# Banker_VHDCI_2_EDGE.net
KiCad netlist of a schematic drawn in Altium Designer
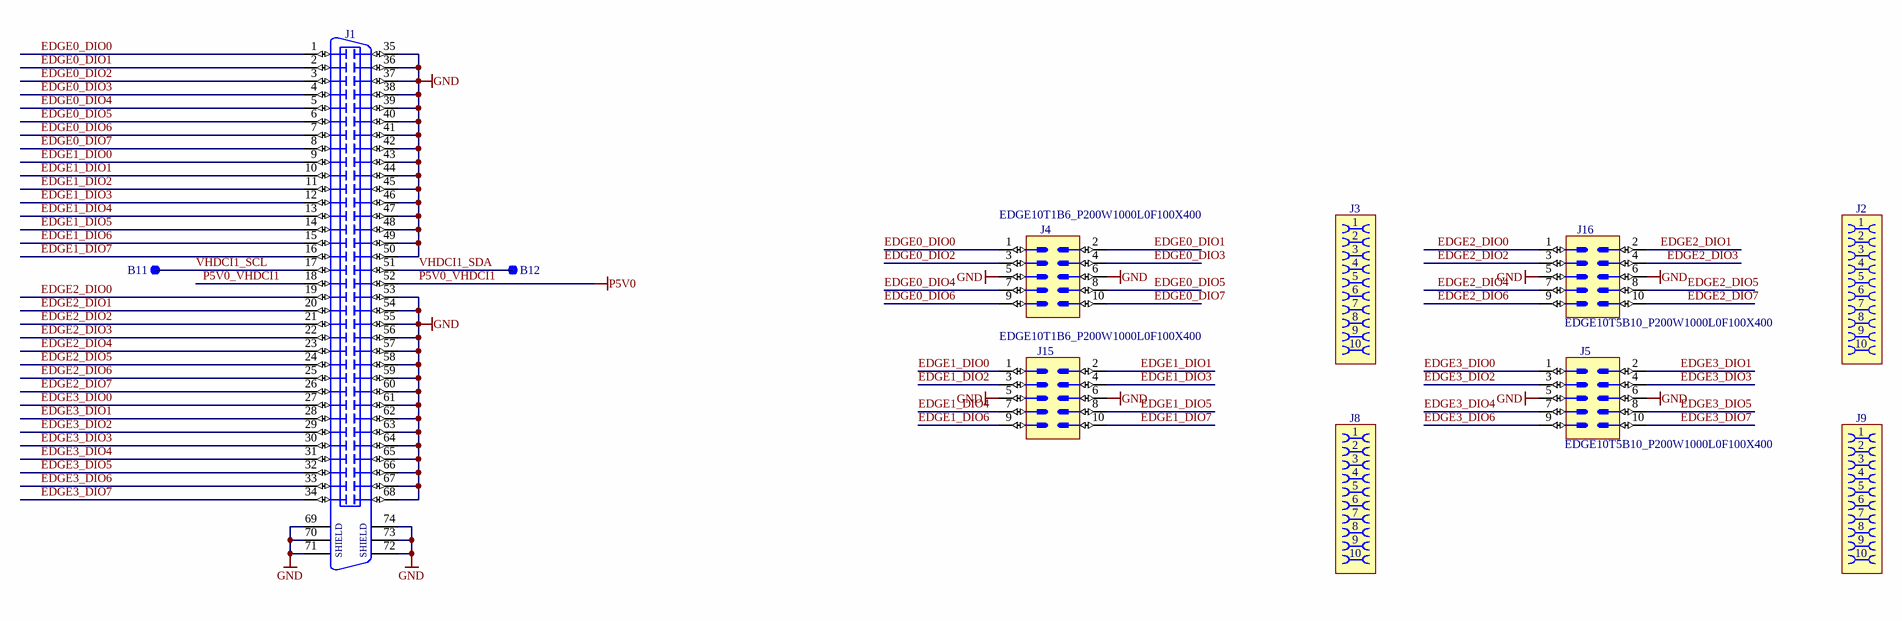
[diagram p0: Banker_VHDCI_2_EDGE.SchDoc]

(export (version "E")
  (design (tool "Eeschema 10.0.6"))
  (components
    (comp (ref "B11")
      (value "SMD Pad")
      (footprint "C100")
      (description "Through Hole Pad")
      (fields (field (name "PART NUMBER") "SMD_PAD_D1MM") (field (name "AUTHOR") "CERN DEM JLC"))
      (libsource (lib "Eletro-mechanical") (part "Single SMD Pad (Round)"))
    )
    (comp (ref "B12")
      (value "SMD Pad")
      (footprint "C100")
      (description "Through Hole Pad")
      (fields (field (name "PART NUMBER") "SMD_PAD_D1MM") (field (name "AUTHOR") "CERN DEM JLC"))
      (libsource (lib "Eletro-mechanical") (part "Single SMD Pad (Round)"))
    )
    (comp (ref "J1")
      (value "VHDCI")
      (footprint "MOLEX_73776-0201")
      (description "0.80mm Pitch, 68 Contacts, Ultra+ VHDCI Surface Mount Vertical Receptacle")
      (fields
        (field (name "PART NUMBER") "MOLEX_73776-0201")
        (field (name "MANUFACTURER") "MOLEX")
        (field (name "AUTHOR") "CERN DEM JLC")
      )
      (libsource (lib "Connectors") (part "MOLEX_73776-0201"))
    )
    (comp (ref "J2")
      (value "~")
      (footprint "AVX_00 9159 010 061 916")
      (description "Open Ended Card Edge Connector, 9159 Series")
      (fields
        (field (name "PART NUMBER") "AVX_00 9159 010 061 916")
        (field (name "MANUFACTURER") "AVX")
        (field (name "AUTHOR") "CERN DEM MR")
      )
      (libsource (lib "Connectors") (part "AVX_00 9159 010 061 916"))
    )
    (comp (ref "J3")
      (value "~")
      (footprint "AVX_00 9159 010 061 916")
      (description "Open Ended Card Edge Connector, 9159 Series")
      (fields
        (field (name "PART NUMBER") "AVX_00 9159 010 061 916")
        (field (name "MANUFACTURER") "AVX")
        (field (name "AUTHOR") "CERN DEM MR")
      )
      (libsource (lib "Connectors") (part "AVX_00 9159 010 061 916"))
    )
    (comp (ref "J4")
      (value "~")
      (footprint "EDGE10T1B6_P200W1000L0F100X400")
      (description "PCB Edge Connector 10 (2x5)")
      (fields
        (field (name "PART NUMBER") "EDGE10T1B6_P200W1000L0F100X400")
        (field (name "AUTHOR") "CERN DEM MR")
      )
      (libsource (lib "Connectors") (part "PCB Edge Connector 10 (2x5)"))
    )
    (comp (ref "J5")
      (value "~")
      (footprint "EDGE10T5B10_P200W1000L0F100X400")
      (description "PCB Edge Connector 10 (2x5)")
      (fields
        (field (name "PART NUMBER") "EDGE10T5B10_P200W1000L0F100X400")
        (field (name "AUTHOR") "CERN DEM MR")
      )
      (libsource (lib "Connectors") (part "PCB Edge Connector 10 (2x5)"))
    )
    (comp (ref "J8")
      (value "~")
      (footprint "AVX_00 9159 010 061 916")
      (description "Open Ended Card Edge Connector, 9159 Series")
      (fields
        (field (name "PART NUMBER") "AVX_00 9159 010 061 916")
        (field (name "MANUFACTURER") "AVX")
        (field (name "AUTHOR") "CERN DEM MR")
      )
      (libsource (lib "Connectors") (part "AVX_00 9159 010 061 916"))
    )
    (comp (ref "J9")
      (value "~")
      (footprint "AVX_00 9159 010 061 916")
      (description "Open Ended Card Edge Connector, 9159 Series")
      (fields
        (field (name "PART NUMBER") "AVX_00 9159 010 061 916")
        (field (name "MANUFACTURER") "AVX")
        (field (name "AUTHOR") "CERN DEM MR")
      )
      (libsource (lib "Connectors") (part "AVX_00 9159 010 061 916"))
    )
    (comp (ref "J15")
      (value "~")
      (footprint "EDGE10T1B6_P200W1000L0F100X400")
      (description "PCB Edge Connector 10 (2x5)")
      (fields
        (field (name "PART NUMBER") "EDGE10T1B6_P200W1000L0F100X400")
        (field (name "AUTHOR") "CERN DEM MR")
      )
      (libsource (lib "Connectors") (part "PCB Edge Connector 10 (2x5)"))
    )
    (comp (ref "J16")
      (value "~")
      (footprint "EDGE10T5B10_P200W1000L0F100X400")
      (description "PCB Edge Connector 10 (2x5)")
      (fields
        (field (name "PART NUMBER") "EDGE10T5B10_P200W1000L0F100X400")
        (field (name "AUTHOR") "CERN DEM MR")
      )
      (libsource (lib "Connectors") (part "PCB Edge Connector 10 (2x5)"))
    )
  )
  (nets
    (net (code "1") (name "/EDGE0_DIO0") (class "Default")
      (node (ref "J1") (pin "1") (pinfunction "1_1") (pintype "bidirectional"))
      (node (ref "J4") (pin "1") (pinfunction "1_1") (pintype "bidirectional"))
    )
    (net (code "2") (name "/EDGE0_DIO1") (class "Default")
      (node (ref "J1") (pin "2") (pinfunction "2_2") (pintype "bidirectional"))
      (node (ref "J4") (pin "2") (pinfunction "2_2") (pintype "bidirectional"))
    )
    (net (code "3") (name "/EDGE0_DIO2") (class "Default")
      (node (ref "J1") (pin "3") (pinfunction "3_3") (pintype "bidirectional"))
      (node (ref "J4") (pin "3") (pinfunction "3_3") (pintype "bidirectional"))
    )
    (net (code "4") (name "/EDGE0_DIO3") (class "Default")
      (node (ref "J1") (pin "4") (pinfunction "4_4") (pintype "bidirectional"))
      (node (ref "J4") (pin "4") (pinfunction "4_4") (pintype "bidirectional"))
    )
    (net (code "5") (name "/EDGE0_DIO4") (class "Default")
      (node (ref "J1") (pin "5") (pinfunction "5_5") (pintype "bidirectional"))
      (node (ref "J4") (pin "7") (pinfunction "7_7") (pintype "bidirectional"))
    )
    (net (code "6") (name "/EDGE0_DIO5") (class "Default")
      (node (ref "J1") (pin "6") (pinfunction "6_6") (pintype "bidirectional"))
      (node (ref "J4") (pin "8") (pinfunction "8_8") (pintype "bidirectional"))
    )
    (net (code "7") (name "/EDGE0_DIO6") (class "Default")
      (node (ref "J1") (pin "7") (pinfunction "7_7") (pintype "bidirectional"))
      (node (ref "J4") (pin "9") (pinfunction "9_9") (pintype "bidirectional"))
    )
    (net (code "8") (name "/EDGE0_DIO7") (class "Default")
      (node (ref "J1") (pin "8") (pinfunction "8_8") (pintype "bidirectional"))
      (node (ref "J4") (pin "10") (pinfunction "10_10") (pintype "bidirectional"))
    )
    (net (code "9") (name "/EDGE1_DIO0") (class "Default")
      (node (ref "J1") (pin "9") (pinfunction "9_9") (pintype "bidirectional"))
      (node (ref "J15") (pin "1") (pinfunction "1_1") (pintype "bidirectional"))
    )
    (net (code "10") (name "/EDGE1_DIO1") (class "Default")
      (node (ref "J1") (pin "10") (pinfunction "10_10") (pintype "bidirectional"))
      (node (ref "J15") (pin "2") (pinfunction "2_2") (pintype "bidirectional"))
    )
    (net (code "11") (name "/EDGE1_DIO2") (class "Default")
      (node (ref "J1") (pin "11") (pinfunction "11_11") (pintype "bidirectional"))
      (node (ref "J15") (pin "3") (pinfunction "3_3") (pintype "bidirectional"))
    )
    (net (code "12") (name "/EDGE1_DIO3") (class "Default")
      (node (ref "J1") (pin "12") (pinfunction "12_12") (pintype "bidirectional"))
      (node (ref "J15") (pin "4") (pinfunction "4_4") (pintype "bidirectional"))
    )
    (net (code "13") (name "/EDGE1_DIO4") (class "Default")
      (node (ref "J1") (pin "13") (pinfunction "13_13") (pintype "bidirectional"))
      (node (ref "J15") (pin "7") (pinfunction "7_7") (pintype "bidirectional"))
    )
    (net (code "14") (name "/EDGE1_DIO5") (class "Default")
      (node (ref "J1") (pin "14") (pinfunction "14_14") (pintype "bidirectional"))
      (node (ref "J15") (pin "8") (pinfunction "8_8") (pintype "bidirectional"))
    )
    (net (code "15") (name "/EDGE1_DIO6") (class "Default")
      (node (ref "J1") (pin "15") (pinfunction "15_15") (pintype "bidirectional"))
      (node (ref "J15") (pin "9") (pinfunction "9_9") (pintype "bidirectional"))
    )
    (net (code "16") (name "/EDGE1_DIO7") (class "Default")
      (node (ref "J1") (pin "16") (pinfunction "16_16") (pintype "bidirectional"))
      (node (ref "J15") (pin "10") (pinfunction "10_10") (pintype "bidirectional"))
    )
    (net (code "17") (name "/EDGE2_DIO0") (class "Default")
      (node (ref "J1") (pin "19") (pinfunction "19_19") (pintype "bidirectional"))
      (node (ref "J16") (pin "1") (pinfunction "1_1") (pintype "bidirectional"))
    )
    (net (code "18") (name "/EDGE2_DIO1") (class "Default")
      (node (ref "J1") (pin "20") (pinfunction "20_20") (pintype "bidirectional"))
      (node (ref "J16") (pin "2") (pinfunction "2_2") (pintype "bidirectional"))
    )
    (net (code "19") (name "/EDGE2_DIO2") (class "Default")
      (node (ref "J1") (pin "21") (pinfunction "21_21") (pintype "bidirectional"))
      (node (ref "J16") (pin "3") (pinfunction "3_3") (pintype "bidirectional"))
    )
    (net (code "20") (name "/EDGE2_DIO3") (class "Default")
      (node (ref "J1") (pin "22") (pinfunction "22_22") (pintype "bidirectional"))
      (node (ref "J16") (pin "4") (pinfunction "4_4") (pintype "bidirectional"))
    )
    (net (code "21") (name "/EDGE2_DIO4") (class "Default")
      (node (ref "J1") (pin "23") (pinfunction "23_23") (pintype "bidirectional"))
      (node (ref "J16") (pin "7") (pinfunction "7_7") (pintype "bidirectional"))
    )
    (net (code "22") (name "/EDGE2_DIO5") (class "Default")
      (node (ref "J1") (pin "24") (pinfunction "24_24") (pintype "bidirectional"))
      (node (ref "J16") (pin "8") (pinfunction "8_8") (pintype "bidirectional"))
    )
    (net (code "23") (name "/EDGE2_DIO6") (class "Default")
      (node (ref "J1") (pin "25") (pinfunction "25_25") (pintype "bidirectional"))
      (node (ref "J16") (pin "9") (pinfunction "9_9") (pintype "bidirectional"))
    )
    (net (code "24") (name "/EDGE2_DIO7") (class "Default")
      (node (ref "J1") (pin "26") (pinfunction "26_26") (pintype "bidirectional"))
      (node (ref "J16") (pin "10") (pinfunction "10_10") (pintype "bidirectional"))
    )
    (net (code "25") (name "/EDGE3_DIO0") (class "Default")
      (node (ref "J1") (pin "27") (pinfunction "27_27") (pintype "bidirectional"))
      (node (ref "J5") (pin "1") (pinfunction "1_1") (pintype "bidirectional"))
    )
    (net (code "26") (name "/EDGE3_DIO1") (class "Default")
      (node (ref "J1") (pin "28") (pinfunction "28_28") (pintype "bidirectional"))
      (node (ref "J5") (pin "2") (pinfunction "2_2") (pintype "bidirectional"))
    )
    (net (code "27") (name "/EDGE3_DIO2") (class "Default")
      (node (ref "J1") (pin "29") (pinfunction "29_29") (pintype "bidirectional"))
      (node (ref "J5") (pin "3") (pinfunction "3_3") (pintype "bidirectional"))
    )
    (net (code "28") (name "/EDGE3_DIO3") (class "Default")
      (node (ref "J1") (pin "30") (pinfunction "30_30") (pintype "bidirectional"))
      (node (ref "J5") (pin "4") (pinfunction "4_4") (pintype "bidirectional"))
    )
    (net (code "29") (name "/EDGE3_DIO4") (class "Default")
      (node (ref "J1") (pin "31") (pinfunction "31_31") (pintype "bidirectional"))
      (node (ref "J5") (pin "7") (pinfunction "7_7") (pintype "bidirectional"))
    )
    (net (code "30") (name "/EDGE3_DIO5") (class "Default")
      (node (ref "J1") (pin "32") (pinfunction "32_32") (pintype "bidirectional"))
      (node (ref "J5") (pin "8") (pinfunction "8_8") (pintype "bidirectional"))
    )
    (net (code "31") (name "/EDGE3_DIO6") (class "Default")
      (node (ref "J1") (pin "33") (pinfunction "33_33") (pintype "bidirectional"))
      (node (ref "J5") (pin "9") (pinfunction "9_9") (pintype "bidirectional"))
    )
    (net (code "32") (name "/EDGE3_DIO7") (class "Default")
      (node (ref "J1") (pin "34") (pinfunction "34_34") (pintype "bidirectional"))
      (node (ref "J5") (pin "10") (pinfunction "10_10") (pintype "bidirectional"))
    )
    (net (code "33") (name "/VHDCI1_SCL") (class "Default")
      (node (ref "B11") (pin "1") (pinfunction "1_1") (pintype "bidirectional"))
      (node (ref "J1") (pin "17") (pinfunction "17_17") (pintype "bidirectional"))
    )
    (net (code "34") (name "/VHDCI1_SDA") (class "Default")
      (node (ref "B12") (pin "1") (pinfunction "1_1") (pintype "bidirectional"))
      (node (ref "J1") (pin "51") (pinfunction "51_51") (pintype "bidirectional"))
    )
    (net (code "35") (name "GND") (class "Default")
      (node (ref "J1") (pin "35") (pinfunction "35_35") (pintype "bidirectional"))
      (node (ref "J1") (pin "36") (pinfunction "36_36") (pintype "bidirectional"))
      (node (ref "J1") (pin "37") (pinfunction "37_37") (pintype "bidirectional"))
      (node (ref "J1") (pin "38") (pinfunction "38_38") (pintype "bidirectional"))
      (node (ref "J1") (pin "39") (pinfunction "39_39") (pintype "bidirectional"))
      (node (ref "J1") (pin "40") (pinfunction "40_40") (pintype "bidirectional"))
      (node (ref "J1") (pin "41") (pinfunction "41_41") (pintype "bidirectional"))
      (node (ref "J1") (pin "42") (pinfunction "42_42") (pintype "bidirectional"))
      (node (ref "J1") (pin "43") (pinfunction "43_43") (pintype "bidirectional"))
      (node (ref "J1") (pin "44") (pinfunction "44_44") (pintype "bidirectional"))
      (node (ref "J1") (pin "45") (pinfunction "45_45") (pintype "bidirectional"))
      (node (ref "J1") (pin "46") (pinfunction "46_46") (pintype "bidirectional"))
      (node (ref "J1") (pin "47") (pinfunction "47_47") (pintype "bidirectional"))
      (node (ref "J1") (pin "48") (pinfunction "48_48") (pintype "bidirectional"))
      (node (ref "J1") (pin "49") (pinfunction "49_49") (pintype "bidirectional"))
      (node (ref "J1") (pin "50") (pinfunction "50_50") (pintype "bidirectional"))
      (node (ref "J1") (pin "53") (pinfunction "53_53") (pintype "bidirectional"))
      (node (ref "J1") (pin "54") (pinfunction "54_54") (pintype "bidirectional"))
      (node (ref "J1") (pin "55") (pinfunction "55_55") (pintype "bidirectional"))
      (node (ref "J1") (pin "56") (pinfunction "56_56") (pintype "bidirectional"))
      (node (ref "J1") (pin "57") (pinfunction "57_57") (pintype "bidirectional"))
      (node (ref "J1") (pin "58") (pinfunction "58_58") (pintype "bidirectional"))
      (node (ref "J1") (pin "59") (pinfunction "59_59") (pintype "bidirectional"))
      (node (ref "J1") (pin "60") (pinfunction "60_60") (pintype "bidirectional"))
      (node (ref "J1") (pin "61") (pinfunction "61_61") (pintype "bidirectional"))
      (node (ref "J1") (pin "62") (pinfunction "62_62") (pintype "bidirectional"))
      (node (ref "J1") (pin "63") (pinfunction "63_63") (pintype "bidirectional"))
      (node (ref "J1") (pin "64") (pinfunction "64_64") (pintype "bidirectional"))
      (node (ref "J1") (pin "65") (pinfunction "65_65") (pintype "bidirectional"))
      (node (ref "J1") (pin "66") (pinfunction "66_66") (pintype "bidirectional"))
      (node (ref "J1") (pin "67") (pinfunction "67_67") (pintype "bidirectional"))
      (node (ref "J1") (pin "68") (pinfunction "68_68") (pintype "bidirectional"))
      (node (ref "J1") (pin "69") (pinfunction "69_69") (pintype "passive"))
      (node (ref "J1") (pin "70") (pinfunction "70_70") (pintype "passive"))
      (node (ref "J1") (pin "71") (pinfunction "71_71") (pintype "passive"))
      (node (ref "J1") (pin "72") (pinfunction "72_72") (pintype "passive"))
      (node (ref "J1") (pin "73") (pinfunction "73_73") (pintype "passive"))
      (node (ref "J1") (pin "74") (pinfunction "74_74") (pintype "passive"))
      (node (ref "J15") (pin "5") (pinfunction "5_5") (pintype "bidirectional"))
      (node (ref "J15") (pin "6") (pinfunction "6_6") (pintype "bidirectional"))
      (node (ref "J16") (pin "5") (pinfunction "5_5") (pintype "bidirectional"))
      (node (ref "J16") (pin "6") (pinfunction "6_6") (pintype "bidirectional"))
      (node (ref "J4") (pin "5") (pinfunction "5_5") (pintype "bidirectional"))
      (node (ref "J4") (pin "6") (pinfunction "6_6") (pintype "bidirectional"))
      (node (ref "J5") (pin "5") (pinfunction "5_5") (pintype "bidirectional"))
      (node (ref "J5") (pin "6") (pinfunction "6_6") (pintype "bidirectional"))
    )
    (net (code "36") (name "P5V0") (class "Default")
      (node (ref "J1") (pin "18") (pinfunction "18_18") (pintype "bidirectional"))
      (node (ref "J1") (pin "52") (pinfunction "52_52") (pintype "bidirectional"))
    )
  )
)
